# main.net
KiCad netlist of a schematic drawn in EAGLE
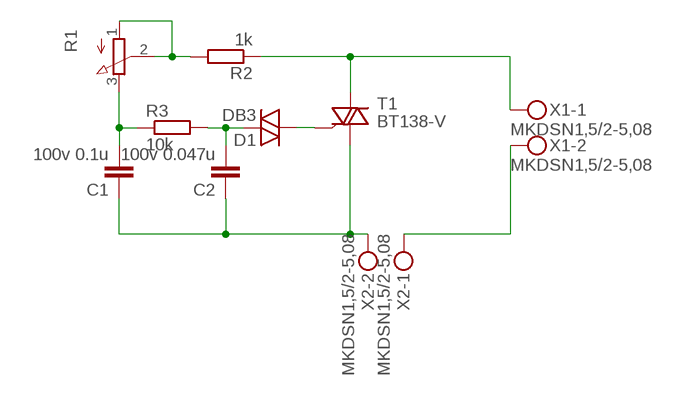
[diagram p0: schematic, sheet 1]

(export (version "E")
  (design (tool "Eeschema 10.0.6"))
  (components
    (comp (ref "C1")
      (value "100v 0.1u")
      (footprint "eagle-import:C102-054X133")
      (libsource (lib "eagle-import") (part "C-EU102-054X133"))
    )
    (comp (ref "C2")
      (value "100v 0.047u")
      (footprint "eagle-import:C075-042X103")
      (libsource (lib "eagle-import") (part "C-EU075-042X103"))
    )
    (comp (ref "D1")
      (value "DB3")
      (footprint "eagle-import:GT32")
      (libsource (lib "eagle-import") (part "DIAC-GT32"))
    )
    (comp (ref "R1")
      (value "3RP/1610N")
      (footprint "eagle-import:3RP_1610N")
      (libsource (lib "eagle-import") (part "3RP/1610N"))
    )
    (comp (ref "R2")
      (value "1k")
      (footprint "eagle-import:0309_10")
      (libsource (lib "eagle-import") (part "R-EU_0309/10"))
    )
    (comp (ref "R3")
      (value "10k")
      (footprint "eagle-import:0309_10")
      (libsource (lib "eagle-import") (part "R-EU_0309/10"))
    )
    (comp (ref "T1")
      (value "BT138-V")
      (footprint "eagle-import:TO220BV")
      (libsource (lib "eagle-import") (part "BT138-V"))
    )
    (comp (ref "X1")
      (value "MKDSN1,5/2-5,08")
      (footprint "eagle-import:MKDSN1,5_2-5,08")
      (libsource (lib "eagle-import") (part "MKDSN1,5/2-5,08"))
    )
    (comp (ref "X2")
      (value "MKDSN1,5/2-5,08")
      (footprint "eagle-import:MKDSN1,5_2-5,08")
      (libsource (lib "eagle-import") (part "MKDSN1,5/2-5,08"))
    )
  )
  (nets
    (net (code "1") (name "Net-(C2-Pad2)") (class "Default")
      (node (ref "C2") (pin "2") (pinfunction "2_2") (pintype "passive"))
      (node (ref "D1") (pin "2") (pinfunction "2_2") (pintype "passive"))
      (node (ref "R3") (pin "2") (pinfunction "2_2") (pintype "passive"))
    )
    (net (code "2") (name "Net-(D1-Pad1)") (class "Default")
      (node (ref "D1") (pin "1") (pinfunction "1_1") (pintype "passive"))
      (node (ref "T1") (pin "G") (pinfunction "G_G") (pintype "passive"))
    )
    (net (code "3") (name "Net-(R1-A)") (class "Default")
      (node (ref "R1") (pin "1") (pinfunction "A_1") (pintype "passive"))
      (node (ref "R1") (pin "2") (pinfunction "S_2") (pintype "passive"))
      (node (ref "R2") (pin "2") (pinfunction "2_2") (pintype "passive"))
    )
    (net (code "4") (name "Net-(R1-E)") (class "Default")
      (node (ref "C1") (pin "2") (pinfunction "2_2") (pintype "passive"))
      (node (ref "R1") (pin "3") (pinfunction "E_3") (pintype "passive"))
      (node (ref "R3") (pin "1") (pinfunction "1_1") (pintype "passive"))
    )
    (net (code "5") (name "Net-(T1-A1)") (class "Default")
      (node (ref "C1") (pin "1") (pinfunction "1_1") (pintype "passive"))
      (node (ref "C2") (pin "1") (pinfunction "1_1") (pintype "passive"))
      (node (ref "T1") (pin "T1") (pinfunction "A1_T1") (pintype "passive"))
      (node (ref "X2") (pin "2") (pinfunction "KL_2") (pintype "passive"))
    )
    (net (code "6") (name "Net-(T1-A2)") (class "Default")
      (node (ref "R2") (pin "1") (pinfunction "1_1") (pintype "passive"))
      (node (ref "T1") (pin "T2") (pinfunction "A2_T2") (pintype "passive"))
      (node (ref "X1") (pin "1") (pinfunction "KL_1") (pintype "passive"))
    )
    (net (code "7") (name "Net-(X1B-KL)") (class "Default")
      (node (ref "X1") (pin "2") (pinfunction "KL_2") (pintype "passive"))
      (node (ref "X2") (pin "1") (pinfunction "KL_1") (pintype "passive"))
    )
  )
)
